# GPIO.net
KiCad netlist of a schematic drawn in Altium Designer
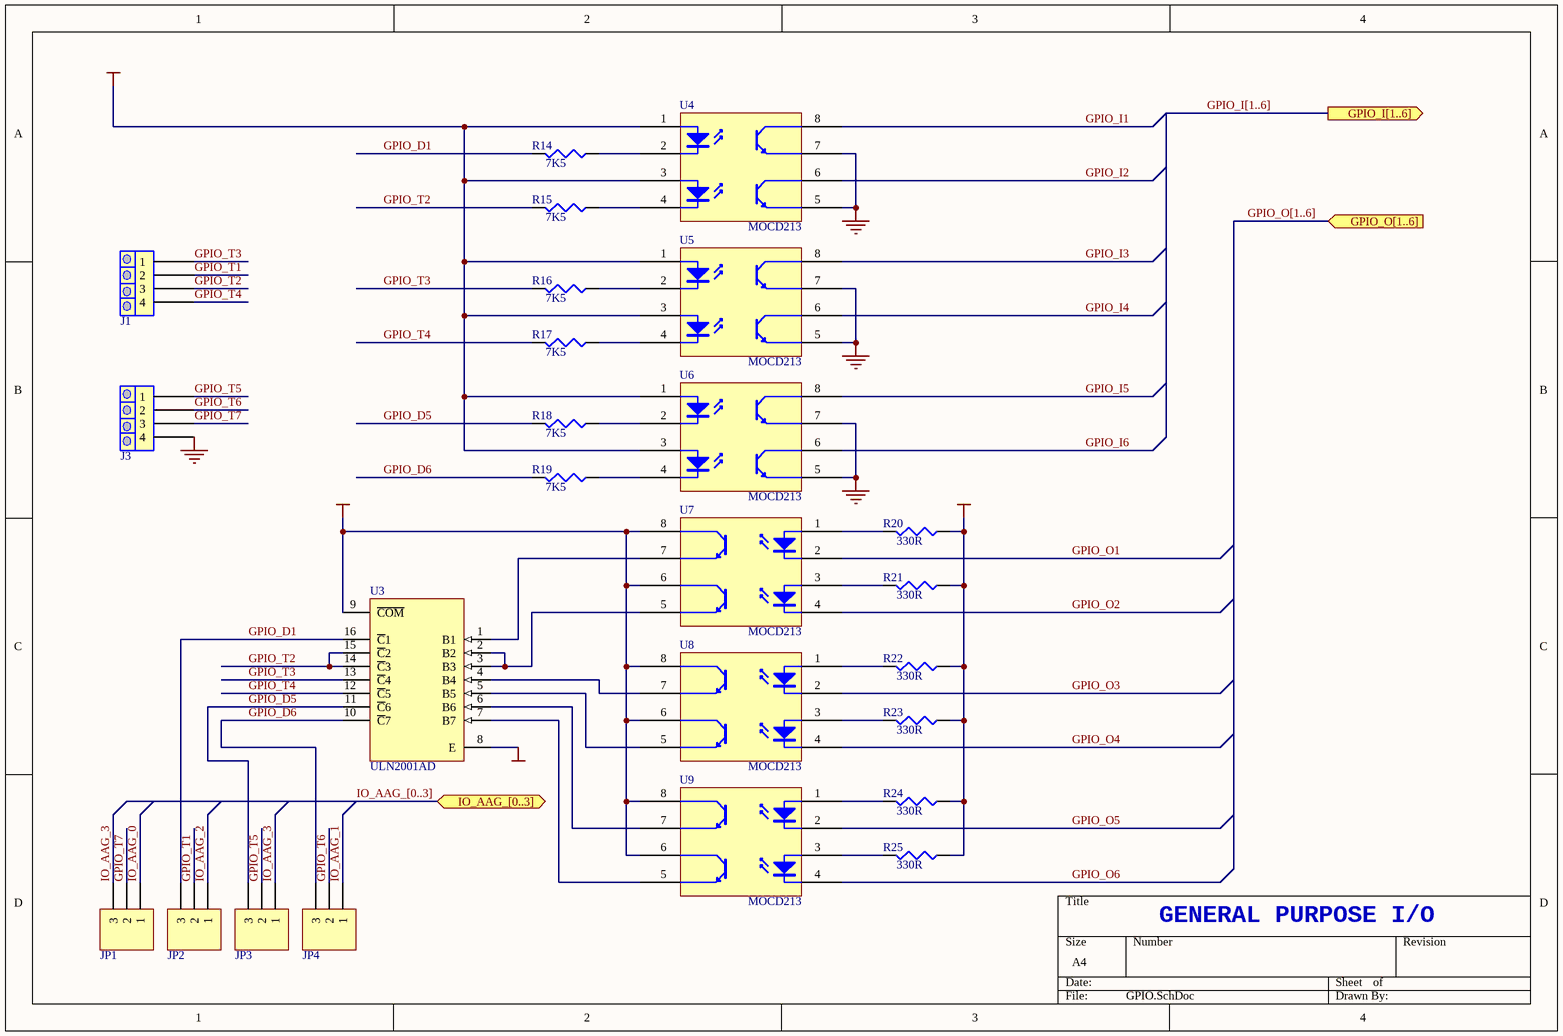
[diagram p0: GPIO.SchDoc]

(export (version "E")
  (design (tool "Eeschema 10.0.6"))
  (components
    (comp (ref "J1")
      (value "BORNERA_X4")
      (footprint "BORNERA_X4")
      (libsource (lib "Custom") (part "BORNERA_X4"))
    )
    (comp (ref "J3")
      (value "BORNERA_X4")
      (footprint "BORNERA_X4")
      (libsource (lib "Custom") (part "BORNERA_X4"))
    )
    (comp (ref "JP1")
      (value "Header 3")
      (footprint "HDR1X3")
      (description "Header, 3-Pin")
      (fields (field (name "PUBLISHER") "Altium Limited"))
      (libsource (lib "Miscellaneous Connectors") (part "Header 3"))
    )
    (comp (ref "JP2")
      (value "Header 3")
      (footprint "HDR1X3")
      (description "Header, 3-Pin")
      (fields (field (name "PUBLISHER") "Altium Limited"))
      (libsource (lib "Miscellaneous Connectors") (part "Header 3"))
    )
    (comp (ref "JP3")
      (value "Header 3")
      (footprint "HDR1X3")
      (description "Header, 3-Pin")
      (fields (field (name "PUBLISHER") "Altium Limited"))
      (libsource (lib "Miscellaneous Connectors") (part "Header 3"))
    )
    (comp (ref "JP4")
      (value "Header 3")
      (footprint "HDR1X3")
      (description "Header, 3-Pin")
      (fields (field (name "PUBLISHER") "Altium Limited"))
      (libsource (lib "Miscellaneous Connectors") (part "Header 3"))
    )
    (comp (ref "R14")
      (value "7K5")
      (footprint "_0805")
      (description "Resistor")
      (fields (field (name "Comment") "Res3") (field (name "PUBLISHER") "Altium Limited"))
      (libsource (lib "Miscellaneous Devices") (part "Res3"))
    )
    (comp (ref "R15")
      (value "7K5")
      (footprint "_0805")
      (description "Resistor")
      (fields (field (name "Comment") "Res3") (field (name "PUBLISHER") "Altium Limited"))
      (libsource (lib "Miscellaneous Devices") (part "Res3"))
    )
    (comp (ref "R16")
      (value "7K5")
      (footprint "_0805")
      (description "Resistor")
      (fields (field (name "Comment") "Res3") (field (name "PUBLISHER") "Altium Limited"))
      (libsource (lib "Miscellaneous Devices") (part "Res3"))
    )
    (comp (ref "R17")
      (value "7K5")
      (footprint "_0805")
      (description "Resistor")
      (fields (field (name "Comment") "Res3") (field (name "PUBLISHER") "Altium Limited"))
      (libsource (lib "Miscellaneous Devices") (part "Res3"))
    )
    (comp (ref "R18")
      (value "7K5")
      (footprint "_0805")
      (description "Resistor")
      (fields (field (name "Comment") "Res3") (field (name "PUBLISHER") "Altium Limited"))
      (libsource (lib "Miscellaneous Devices") (part "Res3"))
    )
    (comp (ref "R19")
      (value "7K5")
      (footprint "_0805")
      (description "Resistor")
      (fields (field (name "Comment") "Res3") (field (name "PUBLISHER") "Altium Limited"))
      (libsource (lib "Miscellaneous Devices") (part "Res3"))
    )
    (comp (ref "R20")
      (value "330R")
      (footprint "_0805")
      (description "Resistor")
      (fields (field (name "Comment") "Res3") (field (name "PUBLISHER") "Altium Limited"))
      (libsource (lib "Miscellaneous Devices") (part "Res3"))
    )
    (comp (ref "R21")
      (value "330R")
      (footprint "_0805")
      (description "Resistor")
      (fields (field (name "Comment") "Res3") (field (name "PUBLISHER") "Altium Limited"))
      (libsource (lib "Miscellaneous Devices") (part "Res3"))
    )
    (comp (ref "R22")
      (value "330R")
      (footprint "_0805")
      (description "Resistor")
      (fields (field (name "Comment") "Res3") (field (name "PUBLISHER") "Altium Limited"))
      (libsource (lib "Miscellaneous Devices") (part "Res3"))
    )
    (comp (ref "R23")
      (value "330R")
      (footprint "_0805")
      (description "Resistor")
      (fields (field (name "Comment") "Res3") (field (name "PUBLISHER") "Altium Limited"))
      (libsource (lib "Miscellaneous Devices") (part "Res3"))
    )
    (comp (ref "R24")
      (value "330R")
      (footprint "_0805")
      (description "Resistor")
      (fields (field (name "Comment") "Res3") (field (name "PUBLISHER") "Altium Limited"))
      (libsource (lib "Miscellaneous Devices") (part "Res3"))
    )
    (comp (ref "R25")
      (value "330R")
      (footprint "_0805")
      (description "Resistor")
      (fields (field (name "Comment") "Res3") (field (name "PUBLISHER") "Altium Limited"))
      (libsource (lib "Miscellaneous Devices") (part "Res3"))
    )
    (comp (ref "U3")
      (value "ULN2001AD")
      (footprint "D016")
      (description "Darlington Transistor Array")
      (fields (field (name "PUBLISHER") "Altium Limited"))
      (libsource (lib "TI Interface Darlington Driver") (part "ULN2003AD"))
    )
    (comp (ref "U4")
      (value "MOCD213")
      (footprint "SO-G8/D5")
      (description "Dual Channel Phototransistor")
      (libsource (lib "Custom") (part "MOCD213"))
    )
    (comp (ref "U5")
      (value "MOCD213")
      (footprint "SO-G8/D5")
      (description "Dual Channel Phototransistor")
      (libsource (lib "Custom") (part "MOCD213"))
    )
    (comp (ref "U6")
      (value "MOCD213")
      (footprint "SO-G8/D5")
      (description "Dual Channel Phototransistor")
      (libsource (lib "Custom") (part "MOCD213"))
    )
    (comp (ref "U7")
      (value "MOCD213")
      (footprint "SO-G8/D5")
      (description "Dual Channel Phototransistor")
      (libsource (lib "") (part "MOCD213_1"))
    )
    (comp (ref "U8")
      (value "MOCD213")
      (footprint "SO-G8/D5")
      (description "Dual Channel Phototransistor")
      (libsource (lib "") (part "MOCD213_1"))
    )
    (comp (ref "U9")
      (value "MOCD213")
      (footprint "SO-G8/D5")
      (description "Dual Channel Phototransistor")
      (libsource (lib "") (part "MOCD213_1"))
    )
  )
  (nets
    (net (code "1") (name "/GPIO_D1") (class "Default")
      (node (ref "JP2") (pin "3") (pinfunction "3_3") (pintype "passive"))
      (node (ref "R14") (pin "2") (pinfunction "2_2") (pintype "passive"))
      (node (ref "U3") (pin "16") (pinfunction "~{C}1_16") (pintype "open_collector"))
    )
    (net (code "2") (name "/GPIO_D5") (class "Default")
      (node (ref "JP3") (pin "3") (pinfunction "3_3") (pintype "passive"))
      (node (ref "R18") (pin "2") (pinfunction "2_2") (pintype "passive"))
      (node (ref "U3") (pin "11") (pinfunction "~{C}6_11") (pintype "open_collector"))
    )
    (net (code "3") (name "/GPIO_D6") (class "Default")
      (node (ref "JP4") (pin "3") (pinfunction "3_3") (pintype "passive"))
      (node (ref "R19") (pin "2") (pinfunction "2_2") (pintype "passive"))
      (node (ref "U3") (pin "10") (pinfunction "~{C}7_10") (pintype "open_collector"))
    )
    (net (code "4") (name "/GPIO_I1") (class "Default")
      (node (ref "U4") (pin "8") (pinfunction "8_8") (pintype "passive"))
    )
    (net (code "5") (name "/GPIO_I2") (class "Default")
      (node (ref "U4") (pin "6") (pinfunction "6_6") (pintype "passive"))
    )
    (net (code "6") (name "/GPIO_I3") (class "Default")
      (node (ref "U5") (pin "8") (pinfunction "8_8") (pintype "passive"))
    )
    (net (code "7") (name "/GPIO_I4") (class "Default")
      (node (ref "U5") (pin "6") (pinfunction "6_6") (pintype "passive"))
    )
    (net (code "8") (name "/GPIO_I5") (class "Default")
      (node (ref "U6") (pin "8") (pinfunction "8_8") (pintype "passive"))
    )
    (net (code "9") (name "/GPIO_I6") (class "Default")
      (node (ref "U6") (pin "6") (pinfunction "6_6") (pintype "passive"))
    )
    (net (code "11") (name "/GPIO_O1") (class "Default")
      (node (ref "U7") (pin "2") (pinfunction "2_2") (pintype "passive"))
    )
    (net (code "12") (name "/GPIO_O2") (class "Default")
      (node (ref "U7") (pin "4") (pinfunction "4_4") (pintype "passive"))
    )
    (net (code "13") (name "/GPIO_O3") (class "Default")
      (node (ref "U8") (pin "2") (pinfunction "2_2") (pintype "passive"))
    )
    (net (code "14") (name "/GPIO_O4") (class "Default")
      (node (ref "U8") (pin "4") (pinfunction "4_4") (pintype "passive"))
    )
    (net (code "15") (name "/GPIO_O5") (class "Default")
      (node (ref "U9") (pin "2") (pinfunction "2_2") (pintype "passive"))
    )
    (net (code "16") (name "/GPIO_O6") (class "Default")
      (node (ref "U9") (pin "4") (pinfunction "4_4") (pintype "passive"))
    )
    (net (code "18") (name "/GPIO_T1") (class "Default")
      (node (ref "J1") (pin "2") (pinfunction "2_2") (pintype "passive"))
      (node (ref "JP2") (pin "2") (pinfunction "2_2") (pintype "passive"))
    )
    (net (code "19") (name "/GPIO_T2") (class "Default")
      (node (ref "J1") (pin "3") (pinfunction "3_3") (pintype "passive"))
      (node (ref "R15") (pin "2") (pinfunction "2_2") (pintype "passive"))
      (node (ref "U3") (pin "14") (pinfunction "~{C}3_14") (pintype "open_collector"))
      (node (ref "U3") (pin "15") (pinfunction "~{C}2_15") (pintype "open_collector"))
    )
    (net (code "20") (name "/GPIO_T3") (class "Default")
      (node (ref "J1") (pin "1") (pinfunction "1_1") (pintype "passive"))
      (node (ref "R16") (pin "2") (pinfunction "2_2") (pintype "passive"))
      (node (ref "U3") (pin "13") (pinfunction "~{C}4_13") (pintype "open_collector"))
    )
    (net (code "21") (name "/GPIO_T4") (class "Default")
      (node (ref "J1") (pin "4") (pinfunction "4_4") (pintype "passive"))
      (node (ref "R17") (pin "2") (pinfunction "2_2") (pintype "passive"))
      (node (ref "U3") (pin "12") (pinfunction "~{C}5_12") (pintype "open_collector"))
    )
    (net (code "22") (name "/GPIO_T5") (class "Default")
      (node (ref "J3") (pin "1") (pinfunction "1_1") (pintype "passive"))
      (node (ref "JP3") (pin "2") (pinfunction "2_2") (pintype "passive"))
    )
    (net (code "23") (name "/GPIO_T6") (class "Default")
      (node (ref "J3") (pin "2") (pinfunction "2_2") (pintype "passive"))
      (node (ref "JP4") (pin "2") (pinfunction "2_2") (pintype "passive"))
    )
    (net (code "24") (name "/GPIO_T7") (class "Default")
      (node (ref "J3") (pin "3") (pinfunction "3_3") (pintype "passive"))
      (node (ref "JP1") (pin "2") (pinfunction "2_2") (pintype "passive"))
    )
    (net (code "25") (name "/IO_AAG_0") (class "Default")
      (node (ref "JP1") (pin "1") (pinfunction "1_1") (pintype "passive"))
    )
    (net (code "26") (name "/IO_AAG_1") (class "Default")
      (node (ref "JP4") (pin "1") (pinfunction "1_1") (pintype "passive"))
    )
    (net (code "27") (name "/IO_AAG_2") (class "Default")
      (node (ref "JP2") (pin "1") (pinfunction "1_1") (pintype "passive"))
    )
    (net (code "28") (name "/IO_AAG_3") (class "Default")
      (node (ref "JP1") (pin "3") (pinfunction "3_3") (pintype "passive"))
      (node (ref "JP3") (pin "1") (pinfunction "1_1") (pintype "passive"))
    )
    (net (code "30") (name "GND") (class "Default")
      (node (ref "J3") (pin "4") (pinfunction "4_4") (pintype "passive"))
      (node (ref "U4") (pin "5") (pinfunction "5_5") (pintype "passive"))
      (node (ref "U4") (pin "7") (pinfunction "7_7") (pintype "passive"))
      (node (ref "U5") (pin "5") (pinfunction "5_5") (pintype "passive"))
      (node (ref "U5") (pin "7") (pinfunction "7_7") (pintype "passive"))
      (node (ref "U6") (pin "5") (pinfunction "5_5") (pintype "passive"))
      (node (ref "U6") (pin "7") (pinfunction "7_7") (pintype "passive"))
    )
    (net (code "31") (name "GND_PWR") (class "Default")
      (node (ref "U3") (pin "8") (pinfunction "E_8") (pintype "power_in"))
    )
    (net (code "32") (name "Net-(R14-Pad1)") (class "Default")
      (node (ref "R14") (pin "1") (pinfunction "1_1") (pintype "passive"))
      (node (ref "U4") (pin "2") (pinfunction "2_2") (pintype "passive"))
    )
    (net (code "33") (name "Net-(R15-Pad1)") (class "Default")
      (node (ref "R15") (pin "1") (pinfunction "1_1") (pintype "passive"))
      (node (ref "U4") (pin "4") (pinfunction "4_4") (pintype "passive"))
    )
    (net (code "34") (name "Net-(R16-Pad1)") (class "Default")
      (node (ref "R16") (pin "1") (pinfunction "1_1") (pintype "passive"))
      (node (ref "U5") (pin "2") (pinfunction "2_2") (pintype "passive"))
    )
    (net (code "35") (name "Net-(R17-Pad1)") (class "Default")
      (node (ref "R17") (pin "1") (pinfunction "1_1") (pintype "passive"))
      (node (ref "U5") (pin "4") (pinfunction "4_4") (pintype "passive"))
    )
    (net (code "36") (name "Net-(R18-Pad1)") (class "Default")
      (node (ref "R18") (pin "1") (pinfunction "1_1") (pintype "passive"))
      (node (ref "U6") (pin "2") (pinfunction "2_2") (pintype "passive"))
    )
    (net (code "37") (name "Net-(R19-Pad1)") (class "Default")
      (node (ref "R19") (pin "1") (pinfunction "1_1") (pintype "passive"))
      (node (ref "U6") (pin "4") (pinfunction "4_4") (pintype "passive"))
    )
    (net (code "38") (name "Net-(R20-Pad2)") (class "Default")
      (node (ref "R20") (pin "2") (pinfunction "2_2") (pintype "passive"))
      (node (ref "U7") (pin "1") (pinfunction "1_1") (pintype "passive"))
    )
    (net (code "39") (name "Net-(R21-Pad2)") (class "Default")
      (node (ref "R21") (pin "2") (pinfunction "2_2") (pintype "passive"))
      (node (ref "U7") (pin "3") (pinfunction "3_3") (pintype "passive"))
    )
    (net (code "40") (name "Net-(R22-Pad2)") (class "Default")
      (node (ref "R22") (pin "2") (pinfunction "2_2") (pintype "passive"))
      (node (ref "U8") (pin "1") (pinfunction "1_1") (pintype "passive"))
    )
    (net (code "41") (name "Net-(R23-Pad2)") (class "Default")
      (node (ref "R23") (pin "2") (pinfunction "2_2") (pintype "passive"))
      (node (ref "U8") (pin "3") (pinfunction "3_3") (pintype "passive"))
    )
    (net (code "42") (name "Net-(R24-Pad2)") (class "Default")
      (node (ref "R24") (pin "2") (pinfunction "2_2") (pintype "passive"))
      (node (ref "U9") (pin "1") (pinfunction "1_1") (pintype "passive"))
    )
    (net (code "43") (name "Net-(R25-Pad2)") (class "Default")
      (node (ref "R25") (pin "2") (pinfunction "2_2") (pintype "passive"))
      (node (ref "U9") (pin "3") (pinfunction "3_3") (pintype "passive"))
    )
    (net (code "44") (name "Net-(U3-B1)") (class "Default")
      (node (ref "U3") (pin "1") (pinfunction "B1_1") (pintype "input"))
      (node (ref "U7") (pin "7") (pinfunction "7_7") (pintype "passive"))
    )
    (net (code "45") (name "Net-(U3-B2)") (class "Default")
      (node (ref "U3") (pin "2") (pinfunction "B2_2") (pintype "input"))
      (node (ref "U3") (pin "3") (pinfunction "B3_3") (pintype "input"))
      (node (ref "U7") (pin "5") (pinfunction "5_5") (pintype "passive"))
    )
    (net (code "46") (name "Net-(U3-B4)") (class "Default")
      (node (ref "U3") (pin "4") (pinfunction "B4_4") (pintype "input"))
      (node (ref "U8") (pin "7") (pinfunction "7_7") (pintype "passive"))
    )
    (net (code "47") (name "Net-(U3-B5)") (class "Default")
      (node (ref "U3") (pin "5") (pinfunction "B5_5") (pintype "input"))
      (node (ref "U8") (pin "5") (pinfunction "5_5") (pintype "passive"))
    )
    (net (code "48") (name "Net-(U3-B6)") (class "Default")
      (node (ref "U3") (pin "6") (pinfunction "B6_6") (pintype "input"))
      (node (ref "U9") (pin "7") (pinfunction "7_7") (pintype "passive"))
    )
    (net (code "49") (name "Net-(U3-B7)") (class "Default")
      (node (ref "U3") (pin "7") (pinfunction "B7_7") (pintype "input"))
      (node (ref "U9") (pin "5") (pinfunction "5_5") (pintype "passive"))
    )
    (net (code "50") (name "VCC_3V") (class "Default")
      (node (ref "R20") (pin "1") (pinfunction "1_1") (pintype "passive"))
      (node (ref "R21") (pin "1") (pinfunction "1_1") (pintype "passive"))
      (node (ref "R22") (pin "1") (pinfunction "1_1") (pintype "passive"))
      (node (ref "R23") (pin "1") (pinfunction "1_1") (pintype "passive"))
      (node (ref "R24") (pin "1") (pinfunction "1_1") (pintype "passive"))
      (node (ref "R25") (pin "1") (pinfunction "1_1") (pintype "passive"))
    )
    (net (code "51") (name "VCC_PWR") (class "Default")
      (node (ref "U3") (pin "9") (pinfunction "~{COM}_9") (pintype "passive"))
      (node (ref "U4") (pin "1") (pinfunction "1_1") (pintype "passive"))
      (node (ref "U4") (pin "3") (pinfunction "3_3") (pintype "passive"))
      (node (ref "U5") (pin "1") (pinfunction "1_1") (pintype "passive"))
      (node (ref "U5") (pin "3") (pinfunction "3_3") (pintype "passive"))
      (node (ref "U6") (pin "1") (pinfunction "1_1") (pintype "passive"))
      (node (ref "U6") (pin "3") (pinfunction "3_3") (pintype "passive"))
      (node (ref "U7") (pin "6") (pinfunction "6_6") (pintype "passive"))
      (node (ref "U7") (pin "8") (pinfunction "8_8") (pintype "passive"))
      (node (ref "U8") (pin "6") (pinfunction "6_6") (pintype "passive"))
      (node (ref "U8") (pin "8") (pinfunction "8_8") (pintype "passive"))
      (node (ref "U9") (pin "6") (pinfunction "6_6") (pintype "passive"))
      (node (ref "U9") (pin "8") (pinfunction "8_8") (pintype "passive"))
    )
  )
)
